# dlp_vco_v1_1_3_main.net
KiCad netlist of a schematic drawn in EAGLE
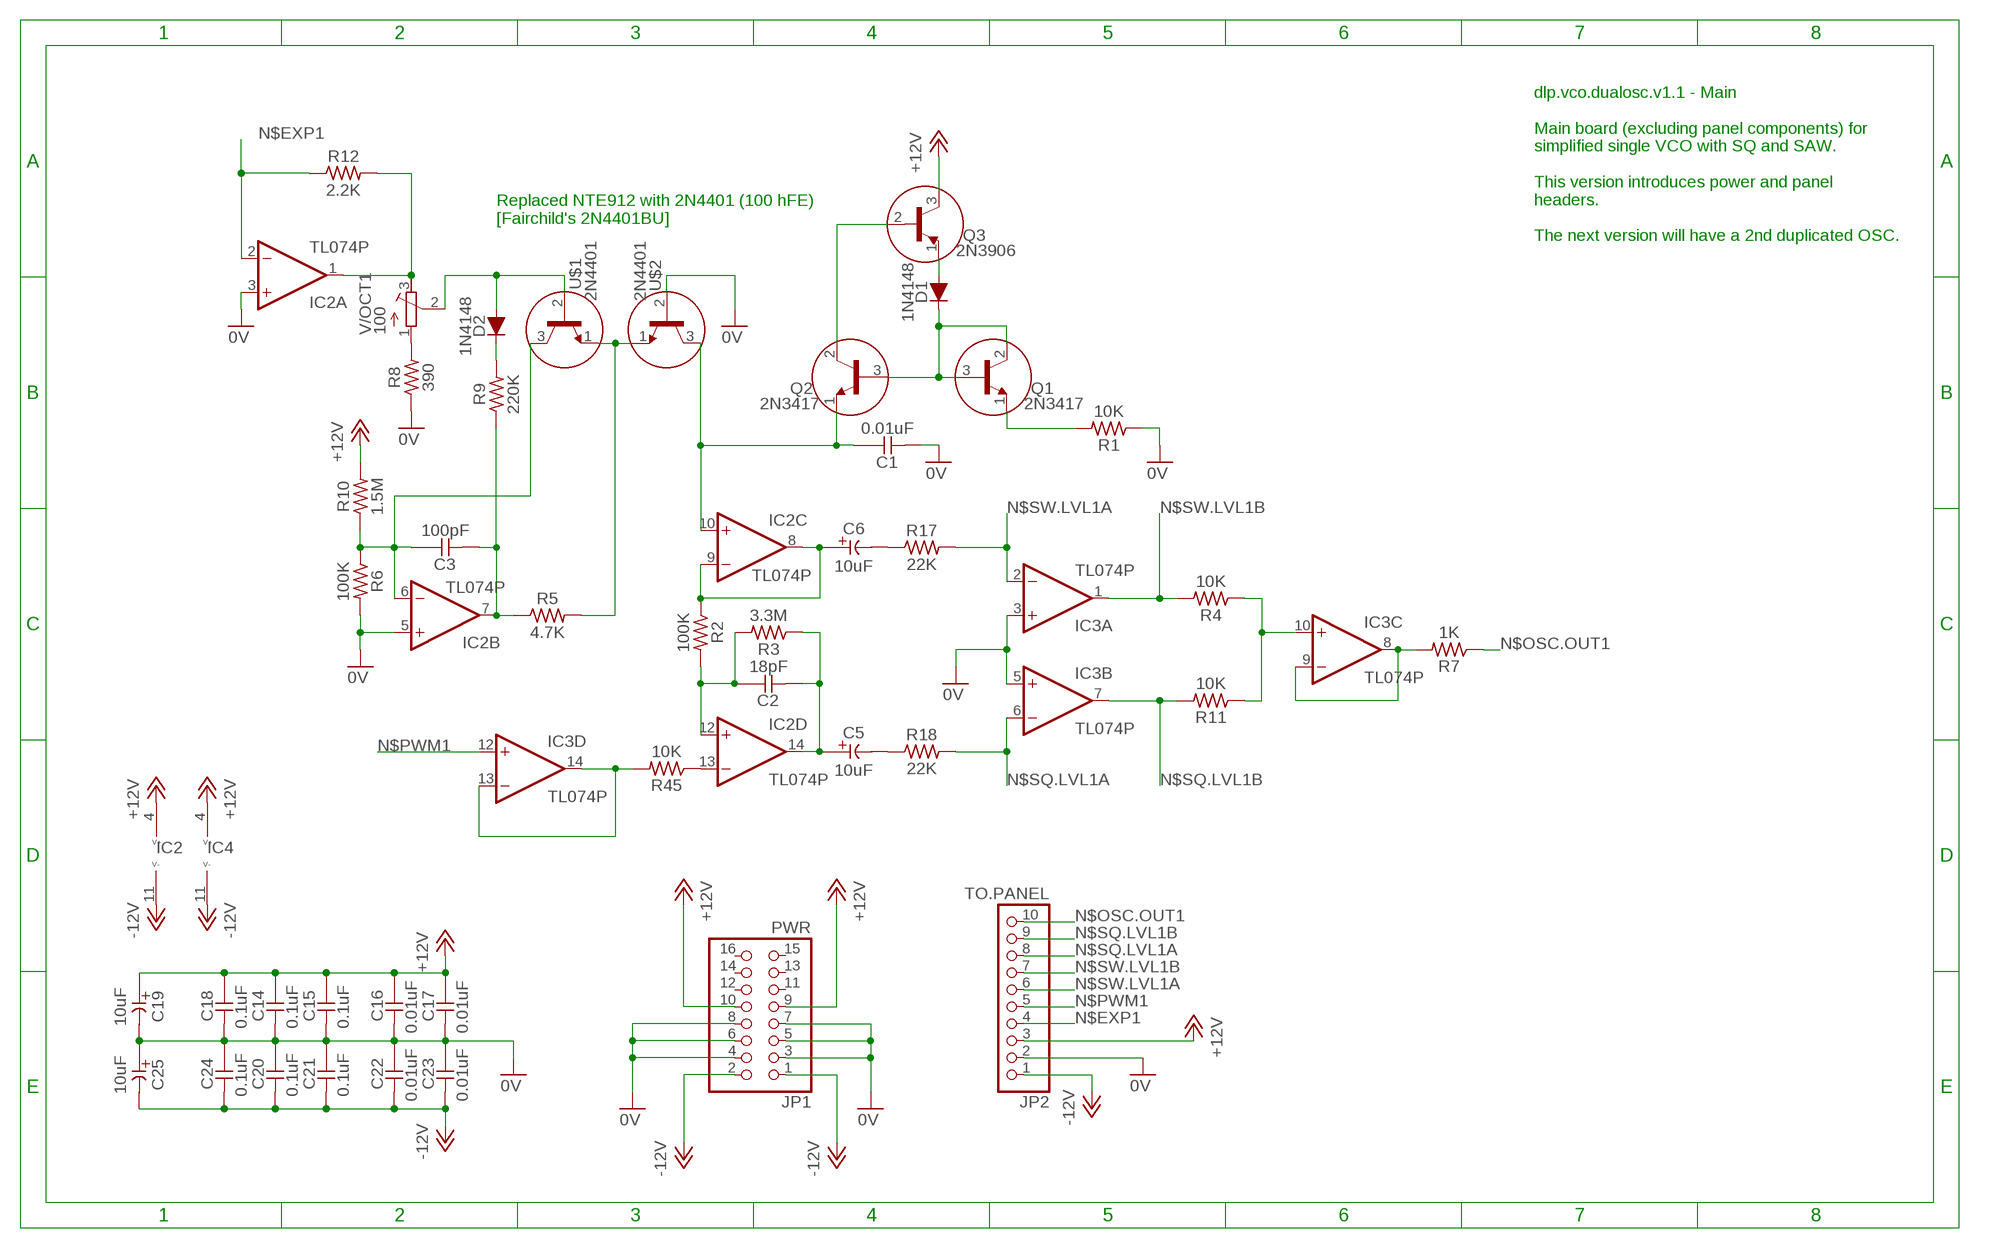
[diagram p0: schematic, sheet 1]

(export (version "E")
  (design (tool "Eeschema 10.0.6"))
  (components
    (comp (ref "C1")
      (value "0.01uF")
      (footprint "eagle-import:C025-024X044")
      (libsource (lib "eagle-import") (part "CC-US025-024X044"))
    )
    (comp (ref "C2")
      (value "18pF")
      (footprint "eagle-import:C025-024X044")
      (libsource (lib "eagle-import") (part "CC-US025-024X044"))
    )
    (comp (ref "C3")
      (value "100pF")
      (footprint "eagle-import:C025-024X044")
      (libsource (lib "eagle-import") (part "CC-US025-024X044"))
    )
    (comp (ref "C5")
      (value "10uF")
      (footprint "eagle-import:E2-5")
      (libsource (lib "eagle-import") (part "CE-USE2-5"))
    )
    (comp (ref "C6")
      (value "10uF")
      (footprint "eagle-import:E2-5")
      (libsource (lib "eagle-import") (part "CE-USE2-5"))
    )
    (comp (ref "C14")
      (value "0.1uF")
      (footprint "eagle-import:C025-024X044")
      (libsource (lib "eagle-import") (part "CC-US025-024X044"))
    )
    (comp (ref "C15")
      (value "0.1uF")
      (footprint "eagle-import:C025-024X044")
      (libsource (lib "eagle-import") (part "CC-US025-024X044"))
    )
    (comp (ref "C16")
      (value "0.01uF")
      (footprint "eagle-import:C025-024X044")
      (libsource (lib "eagle-import") (part "CC-US025-024X044"))
    )
    (comp (ref "C17")
      (value "0.01uF")
      (footprint "eagle-import:C025-024X044")
      (libsource (lib "eagle-import") (part "CC-US025-024X044"))
    )
    (comp (ref "C18")
      (value "0.1uF")
      (footprint "eagle-import:C025-024X044")
      (libsource (lib "eagle-import") (part "CC-US025-024X044"))
    )
    (comp (ref "C19")
      (value "10uF")
      (footprint "eagle-import:E2-5")
      (libsource (lib "eagle-import") (part "CE-USE2-5"))
    )
    (comp (ref "C20")
      (value "0.1uF")
      (footprint "eagle-import:C025-024X044")
      (libsource (lib "eagle-import") (part "CC-US025-024X044"))
    )
    (comp (ref "C21")
      (value "0.1uF")
      (footprint "eagle-import:C025-024X044")
      (libsource (lib "eagle-import") (part "CC-US025-024X044"))
    )
    (comp (ref "C22")
      (value "0.01uF")
      (footprint "eagle-import:C025-024X044")
      (libsource (lib "eagle-import") (part "CC-US025-024X044"))
    )
    (comp (ref "C23")
      (value "0.01uF")
      (footprint "eagle-import:C025-024X044")
      (libsource (lib "eagle-import") (part "CC-US025-024X044"))
    )
    (comp (ref "C24")
      (value "0.1uF")
      (footprint "eagle-import:C025-024X044")
      (libsource (lib "eagle-import") (part "CC-US025-024X044"))
    )
    (comp (ref "C25")
      (value "10uF")
      (footprint "eagle-import:E2-5")
      (libsource (lib "eagle-import") (part "CE-USE2-5"))
    )
    (comp (ref "D1")
      (value "1N4148")
      (footprint "eagle-import:DO35-7")
      (libsource (lib "eagle-import") (part "1N4148"))
    )
    (comp (ref "D2")
      (value "1N4148")
      (footprint "eagle-import:DO35-7")
      (libsource (lib "eagle-import") (part "1N4148"))
    )
    (comp (ref "IC2")
      (value "TL074P")
      (footprint "eagle-import:DIL14")
      (libsource (lib "eagle-import") (part "TL074P"))
    )
    (comp (ref "IC3")
      (value "TL074P")
      (footprint "eagle-import:DIL14")
      (libsource (lib "eagle-import") (part "TL074P"))
    )
    (comp (ref "JP1")
      (value "PWR")
      (footprint "eagle-import:2X08")
      (libsource (lib "eagle-import") (part "PINHD-2X8"))
    )
    (comp (ref "JP2")
      (value "TO.PANEL")
      (footprint "eagle-import:1X10")
      (libsource (lib "eagle-import") (part "PINHD-1X10"))
    )
    (comp (ref "Q1")
      (value "2N3417")
      (footprint "eagle-import:TO92")
      (libsource (lib "eagle-import") (part "2N3417"))
    )
    (comp (ref "Q2")
      (value "2N3417")
      (footprint "eagle-import:TO92")
      (libsource (lib "eagle-import") (part "2N3417"))
    )
    (comp (ref "Q3")
      (value "2N3906")
      (footprint "eagle-import:TO92")
      (libsource (lib "eagle-import") (part "2N3906"))
    )
    (comp (ref "R1")
      (value "10K")
      (footprint "eagle-import:0309_10")
      (libsource (lib "eagle-import") (part "R0309/10"))
    )
    (comp (ref "R2")
      (value "100K")
      (footprint "eagle-import:0309_10")
      (libsource (lib "eagle-import") (part "R0309/10"))
    )
    (comp (ref "R3")
      (value "3.3M")
      (footprint "eagle-import:0309_10")
      (libsource (lib "eagle-import") (part "R0309/10"))
    )
    (comp (ref "R4")
      (value "10K")
      (footprint "eagle-import:0309_10")
      (libsource (lib "eagle-import") (part "R0309/10"))
    )
    (comp (ref "R5")
      (value "4.7K")
      (footprint "eagle-import:0309_10")
      (libsource (lib "eagle-import") (part "R0309/10"))
    )
    (comp (ref "R6")
      (value "100K")
      (footprint "eagle-import:0309_10")
      (libsource (lib "eagle-import") (part "R0309/10"))
    )
    (comp (ref "R7")
      (value "1K")
      (footprint "eagle-import:0309_10")
      (libsource (lib "eagle-import") (part "R0309/10"))
    )
    (comp (ref "R8")
      (value "390")
      (footprint "eagle-import:0309_10")
      (libsource (lib "eagle-import") (part "R0309/10"))
    )
    (comp (ref "R9")
      (value "220K")
      (footprint "eagle-import:0309_10")
      (libsource (lib "eagle-import") (part "R0309/10"))
    )
    (comp (ref "R10")
      (value "1.5M")
      (footprint "eagle-import:0309_10")
      (libsource (lib "eagle-import") (part "R0309/10"))
    )
    (comp (ref "R11")
      (value "10K")
      (footprint "eagle-import:0309_10")
      (libsource (lib "eagle-import") (part "R0309/10"))
    )
    (comp (ref "R12")
      (value "2.2K")
      (footprint "eagle-import:0309_10")
      (libsource (lib "eagle-import") (part "R0309/10"))
    )
    (comp (ref "R17")
      (value "22K")
      (footprint "eagle-import:0309_10")
      (libsource (lib "eagle-import") (part "R0309/10"))
    )
    (comp (ref "R18")
      (value "22K")
      (footprint "eagle-import:0309_10")
      (libsource (lib "eagle-import") (part "R0309/10"))
    )
    (comp (ref "R45")
      (value "10K")
      (footprint "eagle-import:0309_10")
      (libsource (lib "eagle-import") (part "R0309/10"))
    )
    (comp (ref "U$1")
      (value "2N4401")
      (footprint "eagle-import:TO92")
      (libsource (lib "eagle-import") (part "2N4401"))
    )
    (comp (ref "U$2")
      (value "2N4401")
      (footprint "eagle-import:TO92")
      (libsource (lib "eagle-import") (part "2N4401"))
    )
    (comp (ref "V/OCT1")
      (value "100")
      (footprint "eagle-import:RTRIM3296Y")
      (libsource (lib "eagle-import") (part "R-TRIMM3296Y"))
    )
  )
  (nets
    (net (code "1") (name "+12V") (class "Default")
      (node (ref "C14") (pin "1") (pinfunction "1_1") (pintype "passive"))
      (node (ref "C15") (pin "1") (pinfunction "1_1") (pintype "passive"))
      (node (ref "C16") (pin "1") (pinfunction "1_1") (pintype "passive"))
      (node (ref "C17") (pin "1") (pinfunction "1_1") (pintype "passive"))
      (node (ref "C18") (pin "1") (pinfunction "1_1") (pintype "passive"))
      (node (ref "C19") (pin "+") (pinfunction "+_+") (pintype "passive"))
      (node (ref "IC2") (pin "4") (pinfunction "V+_4") (pintype "power_in"))
      (node (ref "IC3") (pin "4") (pinfunction "V+_4") (pintype "power_in"))
      (node (ref "JP1") (pin "10") (pinfunction "10_10") (pintype "passive"))
      (node (ref "JP1") (pin "9") (pinfunction "9_9") (pintype "passive"))
      (node (ref "JP2") (pin "3") (pinfunction "3_3") (pintype "passive"))
      (node (ref "Q3") (pin "3") (pinfunction "C_3") (pintype "passive"))
      (node (ref "R10") (pin "2") (pinfunction "2_2") (pintype "passive"))
    )
    (net (code "2") (name "-12V") (class "Default")
      (node (ref "C20") (pin "2") (pinfunction "2_2") (pintype "passive"))
      (node (ref "C21") (pin "2") (pinfunction "2_2") (pintype "passive"))
      (node (ref "C22") (pin "2") (pinfunction "2_2") (pintype "passive"))
      (node (ref "C23") (pin "2") (pinfunction "2_2") (pintype "passive"))
      (node (ref "C24") (pin "2") (pinfunction "2_2") (pintype "passive"))
      (node (ref "C25") (pin "-") (pinfunction "-_-") (pintype "passive"))
      (node (ref "IC2") (pin "11") (pinfunction "V-_11") (pintype "power_in"))
      (node (ref "IC3") (pin "11") (pinfunction "V-_11") (pintype "power_in"))
      (node (ref "JP1") (pin "1") (pinfunction "1_1") (pintype "passive"))
      (node (ref "JP1") (pin "2") (pinfunction "2_2") (pintype "passive"))
      (node (ref "JP2") (pin "1") (pinfunction "1_1") (pintype "passive"))
    )
    (net (code "3") (name "/N$EXP1") (class "Default")
      (node (ref "IC2") (pin "2") (pinfunction "-IN_2") (pintype "input"))
      (node (ref "JP2") (pin "4") (pinfunction "4_4") (pintype "passive"))
      (node (ref "R12") (pin "1") (pinfunction "1_1") (pintype "passive"))
    )
    (net (code "4") (name "/N$OSC.OUT1") (class "Default")
      (node (ref "JP2") (pin "10") (pinfunction "10_10") (pintype "passive"))
      (node (ref "R7") (pin "1") (pinfunction "1_1") (pintype "passive"))
    )
    (net (code "5") (name "/N$PWM1") (class "Default")
      (node (ref "IC3") (pin "12") (pinfunction "+IN_12") (pintype "input"))
      (node (ref "JP2") (pin "5") (pinfunction "5_5") (pintype "passive"))
    )
    (net (code "6") (name "/N$SQ.LVL1A") (class "Default")
      (node (ref "IC3") (pin "6") (pinfunction "-IN_6") (pintype "input"))
      (node (ref "JP2") (pin "8") (pinfunction "8_8") (pintype "passive"))
      (node (ref "R18") (pin "2") (pinfunction "2_2") (pintype "passive"))
    )
    (net (code "7") (name "/N$SQ.LVL1B") (class "Default")
      (node (ref "IC3") (pin "7") (pinfunction "OUT_7") (pintype "output"))
      (node (ref "JP2") (pin "9") (pinfunction "9_9") (pintype "passive"))
      (node (ref "R11") (pin "2") (pinfunction "2_2") (pintype "passive"))
    )
    (net (code "8") (name "/N$SW.LVL1A") (class "Default")
      (node (ref "IC3") (pin "2") (pinfunction "-IN_2") (pintype "input"))
      (node (ref "JP2") (pin "6") (pinfunction "6_6") (pintype "passive"))
      (node (ref "R17") (pin "2") (pinfunction "2_2") (pintype "passive"))
    )
    (net (code "9") (name "/N$SW.LVL1B") (class "Default")
      (node (ref "IC3") (pin "1") (pinfunction "OUT_1") (pintype "output"))
      (node (ref "JP2") (pin "7") (pinfunction "7_7") (pintype "passive"))
      (node (ref "R4") (pin "2") (pinfunction "2_2") (pintype "passive"))
    )
    (net (code "10") (name "0V") (class "Default")
      (node (ref "C1") (pin "2") (pinfunction "2_2") (pintype "passive"))
      (node (ref "C14") (pin "2") (pinfunction "2_2") (pintype "passive"))
      (node (ref "C15") (pin "2") (pinfunction "2_2") (pintype "passive"))
      (node (ref "C16") (pin "2") (pinfunction "2_2") (pintype "passive"))
      (node (ref "C17") (pin "2") (pinfunction "2_2") (pintype "passive"))
      (node (ref "C18") (pin "2") (pinfunction "2_2") (pintype "passive"))
      (node (ref "C19") (pin "-") (pinfunction "-_-") (pintype "passive"))
      (node (ref "C20") (pin "1") (pinfunction "1_1") (pintype "passive"))
      (node (ref "C21") (pin "1") (pinfunction "1_1") (pintype "passive"))
      (node (ref "C22") (pin "1") (pinfunction "1_1") (pintype "passive"))
      (node (ref "C23") (pin "1") (pinfunction "1_1") (pintype "passive"))
      (node (ref "C24") (pin "1") (pinfunction "1_1") (pintype "passive"))
      (node (ref "C25") (pin "+") (pinfunction "+_+") (pintype "passive"))
      (node (ref "IC2") (pin "3") (pinfunction "+IN_3") (pintype "input"))
      (node (ref "IC2") (pin "5") (pinfunction "+IN_5") (pintype "input"))
      (node (ref "IC3") (pin "3") (pinfunction "+IN_3") (pintype "input"))
      (node (ref "IC3") (pin "5") (pinfunction "+IN_5") (pintype "input"))
      (node (ref "JP1") (pin "3") (pinfunction "3_3") (pintype "passive"))
      (node (ref "JP1") (pin "4") (pinfunction "4_4") (pintype "passive"))
      (node (ref "JP1") (pin "5") (pinfunction "5_5") (pintype "passive"))
      (node (ref "JP1") (pin "6") (pinfunction "6_6") (pintype "passive"))
      (node (ref "JP1") (pin "7") (pinfunction "7_7") (pintype "passive"))
      (node (ref "JP1") (pin "8") (pinfunction "8_8") (pintype "passive"))
      (node (ref "JP2") (pin "2") (pinfunction "2_2") (pintype "passive"))
      (node (ref "R1") (pin "1") (pinfunction "1_1") (pintype "passive"))
      (node (ref "R6") (pin "2") (pinfunction "2_2") (pintype "passive"))
      (node (ref "R8") (pin "1") (pinfunction "1_1") (pintype "passive"))
      (node (ref "U$2") (pin "2") (pinfunction "B_2") (pintype "passive"))
    )
    (net (code "11") (name "Net-(C5-Pad-)") (class "Default")
      (node (ref "C5") (pin "-") (pinfunction "-_-") (pintype "passive"))
      (node (ref "R18") (pin "1") (pinfunction "1_1") (pintype "passive"))
    )
    (net (code "12") (name "Net-(C6-Pad-)") (class "Default")
      (node (ref "C6") (pin "-") (pinfunction "-_-") (pintype "passive"))
      (node (ref "R17") (pin "1") (pinfunction "1_1") (pintype "passive"))
    )
    (net (code "13") (name "Net-(D2-PadC)") (class "Default")
      (node (ref "D2") (pin "C") (pinfunction "C_C") (pintype "passive"))
      (node (ref "R9") (pin "2") (pinfunction "2_2") (pintype "passive"))
    )
    (net (code "14") (name "Net-(IC2A-OUT)") (class "Default")
      (node (ref "IC2") (pin "1") (pinfunction "OUT_1") (pintype "output"))
      (node (ref "R12") (pin "2") (pinfunction "2_2") (pintype "passive"))
      (node (ref "V/OCT1") (pin "3") (pinfunction "E_3") (pintype "passive"))
    )
    (net (code "15") (name "Net-(IC2B--IN)") (class "Default")
      (node (ref "C3") (pin "1") (pinfunction "1_1") (pintype "passive"))
      (node (ref "IC2") (pin "6") (pinfunction "-IN_6") (pintype "input"))
      (node (ref "R10") (pin "1") (pinfunction "1_1") (pintype "passive"))
      (node (ref "R6") (pin "1") (pinfunction "1_1") (pintype "passive"))
      (node (ref "U$1") (pin "3") (pinfunction "C_3") (pintype "passive"))
    )
    (net (code "16") (name "Net-(IC2B-OUT)") (class "Default")
      (node (ref "C3") (pin "2") (pinfunction "2_2") (pintype "passive"))
      (node (ref "IC2") (pin "7") (pinfunction "OUT_7") (pintype "output"))
      (node (ref "R5") (pin "1") (pinfunction "1_1") (pintype "passive"))
      (node (ref "R9") (pin "1") (pinfunction "1_1") (pintype "passive"))
    )
    (net (code "17") (name "Net-(IC2C-+IN)") (class "Default")
      (node (ref "C1") (pin "1") (pinfunction "1_1") (pintype "passive"))
      (node (ref "IC2") (pin "10") (pinfunction "+IN_10") (pintype "input"))
      (node (ref "Q2") (pin "1") (pinfunction "E_1") (pintype "passive"))
      (node (ref "U$2") (pin "3") (pinfunction "C_3") (pintype "passive"))
    )
    (net (code "18") (name "Net-(IC2C--IN)") (class "Default")
      (node (ref "C6") (pin "+") (pinfunction "+_+") (pintype "passive"))
      (node (ref "IC2") (pin "8") (pinfunction "OUT_8") (pintype "output"))
      (node (ref "IC2") (pin "9") (pinfunction "-IN_9") (pintype "input"))
      (node (ref "R2") (pin "1") (pinfunction "1_1") (pintype "passive"))
    )
    (net (code "19") (name "Net-(IC2D-+IN)") (class "Default")
      (node (ref "C2") (pin "1") (pinfunction "1_1") (pintype "passive"))
      (node (ref "IC2") (pin "12") (pinfunction "+IN_12") (pintype "input"))
      (node (ref "R2") (pin "2") (pinfunction "2_2") (pintype "passive"))
      (node (ref "R3") (pin "2") (pinfunction "2_2") (pintype "passive"))
    )
    (net (code "20") (name "Net-(IC2D--IN)") (class "Default")
      (node (ref "IC2") (pin "13") (pinfunction "-IN_13") (pintype "input"))
      (node (ref "R45") (pin "1") (pinfunction "1_1") (pintype "passive"))
    )
    (net (code "21") (name "Net-(IC2D-OUT)") (class "Default")
      (node (ref "C2") (pin "2") (pinfunction "2_2") (pintype "passive"))
      (node (ref "C5") (pin "+") (pinfunction "+_+") (pintype "passive"))
      (node (ref "IC2") (pin "14") (pinfunction "OUT_14") (pintype "output"))
      (node (ref "R3") (pin "1") (pinfunction "1_1") (pintype "passive"))
    )
    (net (code "22") (name "Net-(IC3C-+IN)") (class "Default")
      (node (ref "IC3") (pin "10") (pinfunction "+IN_10") (pintype "input"))
      (node (ref "R11") (pin "1") (pinfunction "1_1") (pintype "passive"))
      (node (ref "R4") (pin "1") (pinfunction "1_1") (pintype "passive"))
    )
    (net (code "23") (name "Net-(IC3C--IN)") (class "Default")
      (node (ref "IC3") (pin "8") (pinfunction "OUT_8") (pintype "output"))
      (node (ref "IC3") (pin "9") (pinfunction "-IN_9") (pintype "input"))
      (node (ref "R7") (pin "2") (pinfunction "2_2") (pintype "passive"))
    )
    (net (code "24") (name "Net-(IC3D--IN)") (class "Default")
      (node (ref "IC3") (pin "13") (pinfunction "-IN_13") (pintype "input"))
      (node (ref "IC3") (pin "14") (pinfunction "OUT_14") (pintype "output"))
      (node (ref "R45") (pin "2") (pinfunction "2_2") (pintype "passive"))
    )
    (net (code "25") (name "Net-(Q1-B)") (class "Default")
      (node (ref "D1") (pin "C") (pinfunction "C_C") (pintype "passive"))
      (node (ref "Q1") (pin "2") (pinfunction "C_2") (pintype "passive"))
      (node (ref "Q1") (pin "3") (pinfunction "B_3") (pintype "passive"))
      (node (ref "Q2") (pin "3") (pinfunction "B_3") (pintype "passive"))
    )
    (net (code "26") (name "Net-(Q1-E)") (class "Default")
      (node (ref "Q1") (pin "1") (pinfunction "E_1") (pintype "passive"))
      (node (ref "R1") (pin "2") (pinfunction "2_2") (pintype "passive"))
    )
    (net (code "27") (name "Net-(Q2-C)") (class "Default")
      (node (ref "Q2") (pin "2") (pinfunction "C_2") (pintype "passive"))
      (node (ref "Q3") (pin "2") (pinfunction "B_2") (pintype "passive"))
    )
    (net (code "28") (name "Net-(Q3-E)") (class "Default")
      (node (ref "D1") (pin "A") (pinfunction "A_A") (pintype "passive"))
      (node (ref "Q3") (pin "1") (pinfunction "E_1") (pintype "passive"))
    )
    (net (code "29") (name "Net-(U$1-B)") (class "Default")
      (node (ref "D2") (pin "A") (pinfunction "A_A") (pintype "passive"))
      (node (ref "U$1") (pin "2") (pinfunction "B_2") (pintype "passive"))
      (node (ref "V/OCT1") (pin "2") (pinfunction "S_2") (pintype "passive"))
    )
    (net (code "30") (name "Net-(U$1-E)") (class "Default")
      (node (ref "R5") (pin "2") (pinfunction "2_2") (pintype "passive"))
      (node (ref "U$1") (pin "1") (pinfunction "E_1") (pintype "passive"))
      (node (ref "U$2") (pin "1") (pinfunction "E_1") (pintype "passive"))
    )
    (net (code "31") (name "Net-(V/OCT1-A)") (class "Default")
      (node (ref "R8") (pin "2") (pinfunction "2_2") (pintype "passive"))
      (node (ref "V/OCT1") (pin "1") (pinfunction "A_1") (pintype "passive"))
    )
    (net (code "32") (name "unconnected-(JP1-Pad11)") (class "Default")
      (node (ref "JP1") (pin "11") (pinfunction "11_11") (pintype "passive"))
    )
    (net (code "33") (name "unconnected-(JP1-Pad12)") (class "Default")
      (node (ref "JP1") (pin "12") (pinfunction "12_12") (pintype "passive"))
    )
    (net (code "34") (name "unconnected-(JP1-Pad13)") (class "Default")
      (node (ref "JP1") (pin "13") (pinfunction "13_13") (pintype "passive"))
    )
    (net (code "35") (name "unconnected-(JP1-Pad14)") (class "Default")
      (node (ref "JP1") (pin "14") (pinfunction "14_14") (pintype "passive"))
    )
    (net (code "36") (name "unconnected-(JP1-Pad15)") (class "Default")
      (node (ref "JP1") (pin "15") (pinfunction "15_15") (pintype "passive"))
    )
    (net (code "37") (name "unconnected-(JP1-Pad16)") (class "Default")
      (node (ref "JP1") (pin "16") (pinfunction "16_16") (pintype "passive"))
    )
  )
)
